# DecadeBox.net
KiCad netlist of a schematic drawn in Altium Designer
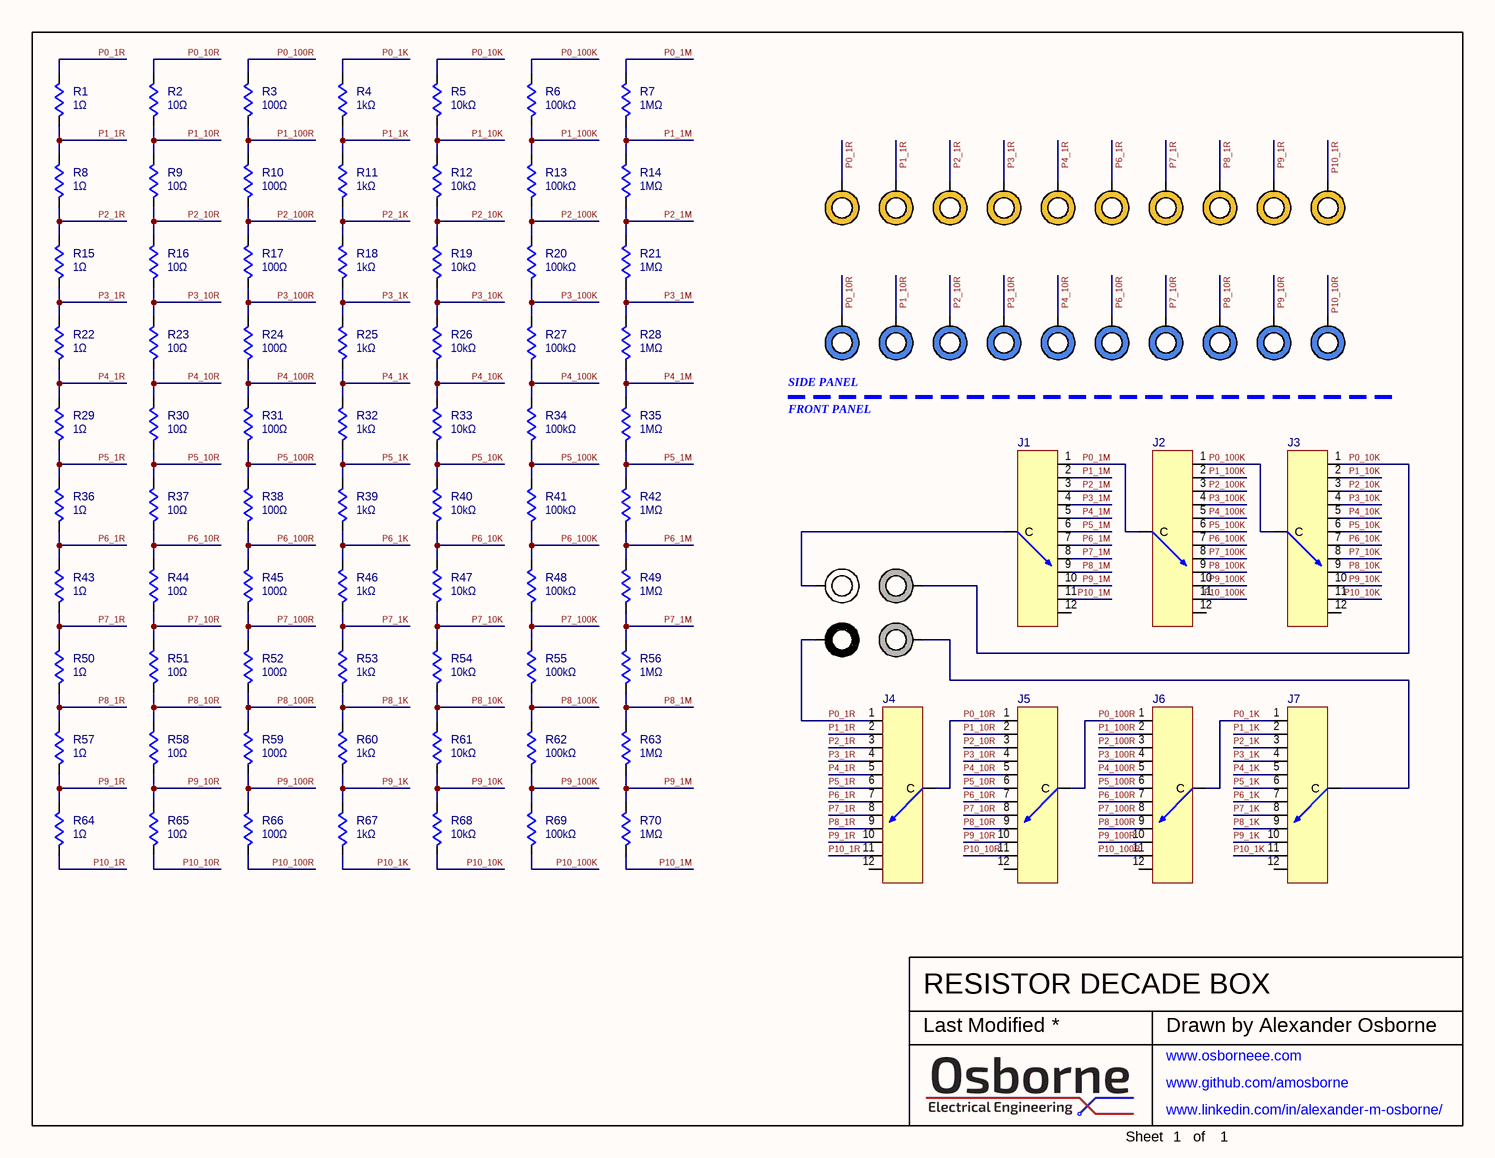
[diagram p0: DecadeBox.SchDoc]

(export (version "E")
  (design (tool "Eeschema 10.0.6"))
  (components
    (comp (ref "J1")
      (value "56SD30-01-1-AJS-ND")
      (description "12 POLE, SINGLE THROW, ROTARY SWITCH")
      (libsource (lib "DecadeBox") (part "ROTARY"))
    )
    (comp (ref "J2")
      (value "56SD30-01-1-AJS-ND")
      (description "12 POLE, SINGLE THROW, ROTARY SWITCH")
      (libsource (lib "DecadeBox") (part "ROTARY"))
    )
    (comp (ref "J3")
      (value "56SD30-01-1-AJS-ND")
      (description "12 POLE, SINGLE THROW, ROTARY SWITCH")
      (libsource (lib "DecadeBox") (part "ROTARY"))
    )
    (comp (ref "J4")
      (value "56SD30-01-1-AJS-ND")
      (description "12 POLE, SINGLE THROW, ROTARY SWITCH")
      (libsource (lib "") (part "ROTARY_1"))
    )
    (comp (ref "J5")
      (value "56SD30-01-1-AJS-ND")
      (description "12 POLE, SINGLE THROW, ROTARY SWITCH")
      (libsource (lib "") (part "ROTARY_1"))
    )
    (comp (ref "J6")
      (value "56SD30-01-1-AJS-ND")
      (description "12 POLE, SINGLE THROW, ROTARY SWITCH")
      (libsource (lib "") (part "ROTARY_1"))
    )
    (comp (ref "J7")
      (value "56SD30-01-1-AJS-ND")
      (description "12 POLE, SINGLE THROW, ROTARY SWITCH")
      (libsource (lib "") (part "ROTARY_1"))
    )
    (comp (ref "J8")
      (value "501-1470-ND")
      (description "BINDING POST, WHITE")
      (libsource (lib "DecadeBox") (part "POST-WHT"))
    )
    (comp (ref "J9")
      (value "501-1714-ND")
      (description "BINDING POST, GRAY")
      (libsource (lib "DecadeBox") (part "POST-GRY"))
    )
    (comp (ref "J10")
      (value "501-2472-ND")
      (description "BINDING POST, BLACK")
      (libsource (lib "DecadeBox") (part "POST-BLK"))
    )
    (comp (ref "J11")
      (value "501-1714-ND")
      (description "BINDING POST, GRAY")
      (libsource (lib "DecadeBox") (part "POST-GRY"))
    )
    (comp (ref "J12")
      (value "501-1082-ND")
      (description "BINDING POST, YELLOW")
      (libsource (lib "DecadeBox") (part "POST-YEL"))
    )
    (comp (ref "J13")
      (value "501-1082-ND")
      (description "BINDING POST, YELLOW")
      (libsource (lib "DecadeBox") (part "POST-YEL"))
    )
    (comp (ref "J14")
      (value "501-1082-ND")
      (description "BINDING POST, YELLOW")
      (libsource (lib "DecadeBox") (part "POST-YEL"))
    )
    (comp (ref "J15")
      (value "501-1082-ND")
      (description "BINDING POST, YELLOW")
      (libsource (lib "DecadeBox") (part "POST-YEL"))
    )
    (comp (ref "J16")
      (value "501-1082-ND")
      (description "BINDING POST, YELLOW")
      (libsource (lib "DecadeBox") (part "POST-YEL"))
    )
    (comp (ref "J17")
      (value "501-1082-ND")
      (description "BINDING POST, YELLOW")
      (libsource (lib "DecadeBox") (part "POST-YEL"))
    )
    (comp (ref "J18")
      (value "501-1082-ND")
      (description "BINDING POST, YELLOW")
      (libsource (lib "DecadeBox") (part "POST-YEL"))
    )
    (comp (ref "J19")
      (value "501-1082-ND")
      (description "BINDING POST, YELLOW")
      (libsource (lib "DecadeBox") (part "POST-YEL"))
    )
    (comp (ref "J20")
      (value "501-1082-ND")
      (description "BINDING POST, YELLOW")
      (libsource (lib "DecadeBox") (part "POST-YEL"))
    )
    (comp (ref "J21")
      (value "501-1082-ND")
      (description "BINDING POST, YELLOW")
      (libsource (lib "DecadeBox") (part "POST-YEL"))
    )
    (comp (ref "J22")
      (value "501-1084-ND")
      (description "BINDING POST, BLUE")
      (libsource (lib "DecadeBox") (part "POST-BLU"))
    )
    (comp (ref "J23")
      (value "501-1084-ND")
      (description "BINDING POST, BLUE")
      (libsource (lib "DecadeBox") (part "POST-BLU"))
    )
    (comp (ref "J24")
      (value "501-1084-ND")
      (description "BINDING POST, BLUE")
      (libsource (lib "DecadeBox") (part "POST-BLU"))
    )
    (comp (ref "J25")
      (value "501-1084-ND")
      (description "BINDING POST, BLUE")
      (libsource (lib "DecadeBox") (part "POST-BLU"))
    )
    (comp (ref "J26")
      (value "501-1084-ND")
      (description "BINDING POST, BLUE")
      (libsource (lib "DecadeBox") (part "POST-BLU"))
    )
    (comp (ref "J27")
      (value "501-1084-ND")
      (description "BINDING POST, BLUE")
      (libsource (lib "DecadeBox") (part "POST-BLU"))
    )
    (comp (ref "J28")
      (value "501-1084-ND")
      (description "BINDING POST, BLUE")
      (libsource (lib "DecadeBox") (part "POST-BLU"))
    )
    (comp (ref "J29")
      (value "501-1084-ND")
      (description "BINDING POST, BLUE")
      (libsource (lib "DecadeBox") (part "POST-BLU"))
    )
    (comp (ref "J30")
      (value "501-1084-ND")
      (description "BINDING POST, BLUE")
      (libsource (lib "DecadeBox") (part "POST-BLU"))
    )
    (comp (ref "J31")
      (value "501-1084-ND")
      (description "BINDING POST, BLUE")
      (libsource (lib "DecadeBox") (part "POST-BLU"))
    )
    (comp (ref "R1")
      (value "1Ω")
      (footprint "MRS25")
      (description "RES 1Ω 1% 50ppm/K 12.5W")
      (fields (field (name "TOLERANCE") "1% + 50ppm/K") (field (name "POWER") "12.5W"))
      (libsource (lib "DecadeBox") (part "RES-1OHM"))
    )
    (comp (ref "R2")
      (value "10Ω")
      (footprint "MRS25")
      (description "RES 10Ω 1% 50ppm/K 10W")
      (fields (field (name "TOLERANCE") "1% + 50ppm/K") (field (name "POWER") "10W"))
      (libsource (lib "DecadeBox") (part "RES-10OHM"))
    )
    (comp (ref "R3")
      (value "100Ω")
      (footprint "MRS25")
      (description "RES 100Ω 1% 50ppm/K 600mW")
      (fields (field (name "TOLERANCE") "1% + 50ppm/K") (field (name "POWER") "600mW"))
      (libsource (lib "DecadeBox") (part "RES-100OHM"))
    )
    (comp (ref "R4")
      (value "1kΩ")
      (footprint "MRS25")
      (description "RES 1kΩ 1% 50ppm/K 600mW")
      (fields (field (name "TOLERANCE") "1% + 50ppm/K") (field (name "POWER") "600mW"))
      (libsource (lib "DecadeBox") (part "RES-1KOHM"))
    )
    (comp (ref "R5")
      (value "10kΩ")
      (footprint "MRS25")
      (description "RES 10kΩ 1% 50ppm/K 600mW")
      (fields (field (name "TOLERANCE") "1% + 50ppm/K") (field (name "POWER") "600mW"))
      (libsource (lib "DecadeBox") (part "RES-10KOHM"))
    )
    (comp (ref "R6")
      (value "100kΩ")
      (footprint "MRS25")
      (description "RES 100kΩ 1% 50ppm/K 600mW")
      (fields (field (name "TOLERANCE") "1% + 50ppm/K") (field (name "POWER") "600mW"))
      (libsource (lib "DecadeBox") (part "RES-100KOHM"))
    )
    (comp (ref "R7")
      (value "1MΩ")
      (footprint "MRS25")
      (description "RES 1MΩ 1% 50ppm/K 600mW")
      (fields (field (name "TOLERANCE") "1% + 50ppm/K") (field (name "POWER") "600mW"))
      (libsource (lib "DecadeBox") (part "RES-1MOHM"))
    )
    (comp (ref "R8")
      (value "1Ω")
      (footprint "MRS25")
      (description "RES 1Ω 1% 50ppm/K 12.5W")
      (fields (field (name "TOLERANCE") "1% + 50ppm/K") (field (name "POWER") "12.5W"))
      (libsource (lib "DecadeBox") (part "RES-1OHM"))
    )
    (comp (ref "R9")
      (value "10Ω")
      (footprint "MRS25")
      (description "RES 10Ω 1% 50ppm/K 10W")
      (fields (field (name "TOLERANCE") "1% + 50ppm/K") (field (name "POWER") "10W"))
      (libsource (lib "DecadeBox") (part "RES-10OHM"))
    )
    (comp (ref "R10")
      (value "100Ω")
      (footprint "MRS25")
      (description "RES 100Ω 1% 50ppm/K 600mW")
      (fields (field (name "TOLERANCE") "1% + 50ppm/K") (field (name "POWER") "600mW"))
      (libsource (lib "DecadeBox") (part "RES-100OHM"))
    )
    (comp (ref "R11")
      (value "1kΩ")
      (footprint "MRS25")
      (description "RES 1kΩ 1% 50ppm/K 600mW")
      (fields (field (name "TOLERANCE") "1% + 50ppm/K") (field (name "POWER") "600mW"))
      (libsource (lib "DecadeBox") (part "RES-1KOHM"))
    )
    (comp (ref "R12")
      (value "10kΩ")
      (footprint "MRS25")
      (description "RES 10kΩ 1% 50ppm/K 600mW")
      (fields (field (name "TOLERANCE") "1% + 50ppm/K") (field (name "POWER") "600mW"))
      (libsource (lib "DecadeBox") (part "RES-10KOHM"))
    )
    (comp (ref "R13")
      (value "100kΩ")
      (footprint "MRS25")
      (description "RES 100kΩ 1% 50ppm/K 600mW")
      (fields (field (name "TOLERANCE") "1% + 50ppm/K") (field (name "POWER") "600mW"))
      (libsource (lib "DecadeBox") (part "RES-100KOHM"))
    )
    (comp (ref "R14")
      (value "1MΩ")
      (footprint "MRS25")
      (description "RES 1MΩ 1% 50ppm/K 600mW")
      (fields (field (name "TOLERANCE") "1% + 50ppm/K") (field (name "POWER") "600mW"))
      (libsource (lib "DecadeBox") (part "RES-1MOHM"))
    )
    (comp (ref "R15")
      (value "1Ω")
      (footprint "MRS25")
      (description "RES 1Ω 1% 50ppm/K 12.5W")
      (fields (field (name "TOLERANCE") "1% + 50ppm/K") (field (name "POWER") "12.5W"))
      (libsource (lib "DecadeBox") (part "RES-1OHM"))
    )
    (comp (ref "R16")
      (value "10Ω")
      (footprint "MRS25")
      (description "RES 10Ω 1% 50ppm/K 10W")
      (fields (field (name "TOLERANCE") "1% + 50ppm/K") (field (name "POWER") "10W"))
      (libsource (lib "DecadeBox") (part "RES-10OHM"))
    )
    (comp (ref "R17")
      (value "100Ω")
      (footprint "MRS25")
      (description "RES 100Ω 1% 50ppm/K 600mW")
      (fields (field (name "TOLERANCE") "1% + 50ppm/K") (field (name "POWER") "600mW"))
      (libsource (lib "DecadeBox") (part "RES-100OHM"))
    )
    (comp (ref "R18")
      (value "1kΩ")
      (footprint "MRS25")
      (description "RES 1kΩ 1% 50ppm/K 600mW")
      (fields (field (name "TOLERANCE") "1% + 50ppm/K") (field (name "POWER") "600mW"))
      (libsource (lib "DecadeBox") (part "RES-1KOHM"))
    )
    (comp (ref "R19")
      (value "10kΩ")
      (footprint "MRS25")
      (description "RES 10kΩ 1% 50ppm/K 600mW")
      (fields (field (name "TOLERANCE") "1% + 50ppm/K") (field (name "POWER") "600mW"))
      (libsource (lib "DecadeBox") (part "RES-10KOHM"))
    )
    (comp (ref "R20")
      (value "100kΩ")
      (footprint "MRS25")
      (description "RES 100kΩ 1% 50ppm/K 600mW")
      (fields (field (name "TOLERANCE") "1% + 50ppm/K") (field (name "POWER") "600mW"))
      (libsource (lib "DecadeBox") (part "RES-100KOHM"))
    )
    (comp (ref "R21")
      (value "1MΩ")
      (footprint "MRS25")
      (description "RES 1MΩ 1% 50ppm/K 600mW")
      (fields (field (name "TOLERANCE") "1% + 50ppm/K") (field (name "POWER") "600mW"))
      (libsource (lib "DecadeBox") (part "RES-1MOHM"))
    )
    (comp (ref "R22")
      (value "1Ω")
      (footprint "MRS25")
      (description "RES 1Ω 1% 50ppm/K 12.5W")
      (fields (field (name "TOLERANCE") "1% + 50ppm/K") (field (name "POWER") "12.5W"))
      (libsource (lib "DecadeBox") (part "RES-1OHM"))
    )
    (comp (ref "R23")
      (value "10Ω")
      (footprint "MRS25")
      (description "RES 10Ω 1% 50ppm/K 10W")
      (fields (field (name "TOLERANCE") "1% + 50ppm/K") (field (name "POWER") "10W"))
      (libsource (lib "DecadeBox") (part "RES-10OHM"))
    )
    (comp (ref "R24")
      (value "100Ω")
      (footprint "MRS25")
      (description "RES 100Ω 1% 50ppm/K 600mW")
      (fields (field (name "TOLERANCE") "1% + 50ppm/K") (field (name "POWER") "600mW"))
      (libsource (lib "DecadeBox") (part "RES-100OHM"))
    )
    (comp (ref "R25")
      (value "1kΩ")
      (footprint "MRS25")
      (description "RES 1kΩ 1% 50ppm/K 600mW")
      (fields (field (name "TOLERANCE") "1% + 50ppm/K") (field (name "POWER") "600mW"))
      (libsource (lib "DecadeBox") (part "RES-1KOHM"))
    )
    (comp (ref "R26")
      (value "10kΩ")
      (footprint "MRS25")
      (description "RES 10kΩ 1% 50ppm/K 600mW")
      (fields (field (name "TOLERANCE") "1% + 50ppm/K") (field (name "POWER") "600mW"))
      (libsource (lib "DecadeBox") (part "RES-10KOHM"))
    )
    (comp (ref "R27")
      (value "100kΩ")
      (footprint "MRS25")
      (description "RES 100kΩ 1% 50ppm/K 600mW")
      (fields (field (name "TOLERANCE") "1% + 50ppm/K") (field (name "POWER") "600mW"))
      (libsource (lib "DecadeBox") (part "RES-100KOHM"))
    )
    (comp (ref "R28")
      (value "1MΩ")
      (footprint "MRS25")
      (description "RES 1MΩ 1% 50ppm/K 600mW")
      (fields (field (name "TOLERANCE") "1% + 50ppm/K") (field (name "POWER") "600mW"))
      (libsource (lib "DecadeBox") (part "RES-1MOHM"))
    )
    (comp (ref "R29")
      (value "1Ω")
      (footprint "MRS25")
      (description "RES 1Ω 1% 50ppm/K 12.5W")
      (fields (field (name "TOLERANCE") "1% + 50ppm/K") (field (name "POWER") "12.5W"))
      (libsource (lib "DecadeBox") (part "RES-1OHM"))
    )
    (comp (ref "R30")
      (value "10Ω")
      (footprint "MRS25")
      (description "RES 10Ω 1% 50ppm/K 10W")
      (fields (field (name "TOLERANCE") "1% + 50ppm/K") (field (name "POWER") "10W"))
      (libsource (lib "DecadeBox") (part "RES-10OHM"))
    )
    (comp (ref "R31")
      (value "100Ω")
      (footprint "MRS25")
      (description "RES 100Ω 1% 50ppm/K 600mW")
      (fields (field (name "TOLERANCE") "1% + 50ppm/K") (field (name "POWER") "600mW"))
      (libsource (lib "DecadeBox") (part "RES-100OHM"))
    )
    (comp (ref "R32")
      (value "1kΩ")
      (footprint "MRS25")
      (description "RES 1kΩ 1% 50ppm/K 600mW")
      (fields (field (name "TOLERANCE") "1% + 50ppm/K") (field (name "POWER") "600mW"))
      (libsource (lib "DecadeBox") (part "RES-1KOHM"))
    )
    (comp (ref "R33")
      (value "10kΩ")
      (footprint "MRS25")
      (description "RES 10kΩ 1% 50ppm/K 600mW")
      (fields (field (name "TOLERANCE") "1% + 50ppm/K") (field (name "POWER") "600mW"))
      (libsource (lib "DecadeBox") (part "RES-10KOHM"))
    )
    (comp (ref "R34")
      (value "100kΩ")
      (footprint "MRS25")
      (description "RES 100kΩ 1% 50ppm/K 600mW")
      (fields (field (name "TOLERANCE") "1% + 50ppm/K") (field (name "POWER") "600mW"))
      (libsource (lib "DecadeBox") (part "RES-100KOHM"))
    )
    (comp (ref "R35")
      (value "1MΩ")
      (footprint "MRS25")
      (description "RES 1MΩ 1% 50ppm/K 600mW")
      (fields (field (name "TOLERANCE") "1% + 50ppm/K") (field (name "POWER") "600mW"))
      (libsource (lib "DecadeBox") (part "RES-1MOHM"))
    )
    (comp (ref "R36")
      (value "1Ω")
      (footprint "MRS25")
      (description "RES 1Ω 1% 50ppm/K 12.5W")
      (fields (field (name "TOLERANCE") "1% + 50ppm/K") (field (name "POWER") "12.5W"))
      (libsource (lib "DecadeBox") (part "RES-1OHM"))
    )
    (comp (ref "R37")
      (value "10Ω")
      (footprint "MRS25")
      (description "RES 10Ω 1% 50ppm/K 10W")
      (fields (field (name "TOLERANCE") "1% + 50ppm/K") (field (name "POWER") "10W"))
      (libsource (lib "DecadeBox") (part "RES-10OHM"))
    )
    (comp (ref "R38")
      (value "100Ω")
      (footprint "MRS25")
      (description "RES 100Ω 1% 50ppm/K 600mW")
      (fields (field (name "TOLERANCE") "1% + 50ppm/K") (field (name "POWER") "600mW"))
      (libsource (lib "DecadeBox") (part "RES-100OHM"))
    )
    (comp (ref "R39")
      (value "1kΩ")
      (footprint "MRS25")
      (description "RES 1kΩ 1% 50ppm/K 600mW")
      (fields (field (name "TOLERANCE") "1% + 50ppm/K") (field (name "POWER") "600mW"))
      (libsource (lib "DecadeBox") (part "RES-1KOHM"))
    )
    (comp (ref "R40")
      (value "10kΩ")
      (footprint "MRS25")
      (description "RES 10kΩ 1% 50ppm/K 600mW")
      (fields (field (name "TOLERANCE") "1% + 50ppm/K") (field (name "POWER") "600mW"))
      (libsource (lib "DecadeBox") (part "RES-10KOHM"))
    )
    (comp (ref "R41")
      (value "100kΩ")
      (footprint "MRS25")
      (description "RES 100kΩ 1% 50ppm/K 600mW")
      (fields (field (name "TOLERANCE") "1% + 50ppm/K") (field (name "POWER") "600mW"))
      (libsource (lib "DecadeBox") (part "RES-100KOHM"))
    )
    (comp (ref "R42")
      (value "1MΩ")
      (footprint "MRS25")
      (description "RES 1MΩ 1% 50ppm/K 600mW")
      (fields (field (name "TOLERANCE") "1% + 50ppm/K") (field (name "POWER") "600mW"))
      (libsource (lib "DecadeBox") (part "RES-1MOHM"))
    )
    (comp (ref "R43")
      (value "1Ω")
      (footprint "MRS25")
      (description "RES 1Ω 1% 50ppm/K 12.5W")
      (fields (field (name "TOLERANCE") "1% + 50ppm/K") (field (name "POWER") "12.5W"))
      (libsource (lib "DecadeBox") (part "RES-1OHM"))
    )
    (comp (ref "R44")
      (value "10Ω")
      (footprint "MRS25")
      (description "RES 10Ω 1% 50ppm/K 10W")
      (fields (field (name "TOLERANCE") "1% + 50ppm/K") (field (name "POWER") "10W"))
      (libsource (lib "DecadeBox") (part "RES-10OHM"))
    )
    (comp (ref "R45")
      (value "100Ω")
      (footprint "MRS25")
      (description "RES 100Ω 1% 50ppm/K 600mW")
      (fields (field (name "TOLERANCE") "1% + 50ppm/K") (field (name "POWER") "600mW"))
      (libsource (lib "DecadeBox") (part "RES-100OHM"))
    )
    (comp (ref "R46")
      (value "1kΩ")
      (footprint "MRS25")
      (description "RES 1kΩ 1% 50ppm/K 600mW")
      (fields (field (name "TOLERANCE") "1% + 50ppm/K") (field (name "POWER") "600mW"))
      (libsource (lib "DecadeBox") (part "RES-1KOHM"))
    )
    (comp (ref "R47")
      (value "10kΩ")
      (footprint "MRS25")
      (description "RES 10kΩ 1% 50ppm/K 600mW")
      (fields (field (name "TOLERANCE") "1% + 50ppm/K") (field (name "POWER") "600mW"))
      (libsource (lib "DecadeBox") (part "RES-10KOHM"))
    )
    (comp (ref "R48")
      (value "100kΩ")
      (footprint "MRS25")
      (description "RES 100kΩ 1% 50ppm/K 600mW")
      (fields (field (name "TOLERANCE") "1% + 50ppm/K") (field (name "POWER") "600mW"))
      (libsource (lib "DecadeBox") (part "RES-100KOHM"))
    )
    (comp (ref "R49")
      (value "1MΩ")
      (footprint "MRS25")
      (description "RES 1MΩ 1% 50ppm/K 600mW")
      (fields (field (name "TOLERANCE") "1% + 50ppm/K") (field (name "POWER") "600mW"))
      (libsource (lib "DecadeBox") (part "RES-1MOHM"))
    )
    (comp (ref "R50")
      (value "1Ω")
      (footprint "MRS25")
      (description "RES 1Ω 1% 50ppm/K 12.5W")
      (fields (field (name "TOLERANCE") "1% + 50ppm/K") (field (name "POWER") "12.5W"))
      (libsource (lib "DecadeBox") (part "RES-1OHM"))
    )
    (comp (ref "R51")
      (value "10Ω")
      (footprint "MRS25")
      (description "RES 10Ω 1% 50ppm/K 10W")
      (fields (field (name "TOLERANCE") "1% + 50ppm/K") (field (name "POWER") "10W"))
      (libsource (lib "DecadeBox") (part "RES-10OHM"))
    )
    (comp (ref "R52")
      (value "100Ω")
      (footprint "MRS25")
      (description "RES 100Ω 1% 50ppm/K 600mW")
      (fields (field (name "TOLERANCE") "1% + 50ppm/K") (field (name "POWER") "600mW"))
      (libsource (lib "DecadeBox") (part "RES-100OHM"))
    )
    (comp (ref "R53")
      (value "1kΩ")
      (footprint "MRS25")
      (description "RES 1kΩ 1% 50ppm/K 600mW")
      (fields (field (name "TOLERANCE") "1% + 50ppm/K") (field (name "POWER") "600mW"))
      (libsource (lib "DecadeBox") (part "RES-1KOHM"))
    )
    (comp (ref "R54")
      (value "10kΩ")
      (footprint "MRS25")
      (description "RES 10kΩ 1% 50ppm/K 600mW")
      (fields (field (name "TOLERANCE") "1% + 50ppm/K") (field (name "POWER") "600mW"))
      (libsource (lib "DecadeBox") (part "RES-10KOHM"))
    )
    (comp (ref "R55")
      (value "100kΩ")
      (footprint "MRS25")
      (description "RES 100kΩ 1% 50ppm/K 600mW")
      (fields (field (name "TOLERANCE") "1% + 50ppm/K") (field (name "POWER") "600mW"))
      (libsource (lib "DecadeBox") (part "RES-100KOHM"))
    )
    (comp (ref "R56")
      (value "1MΩ")
      (footprint "MRS25")
      (description "RES 1MΩ 1% 50ppm/K 600mW")
      (fields (field (name "TOLERANCE") "1% + 50ppm/K") (field (name "POWER") "600mW"))
      (libsource (lib "DecadeBox") (part "RES-1MOHM"))
    )
    (comp (ref "R57")
      (value "1Ω")
      (footprint "MRS25")
      (description "RES 1Ω 1% 50ppm/K 12.5W")
      (fields (field (name "TOLERANCE") "1% + 50ppm/K") (field (name "POWER") "12.5W"))
      (libsource (lib "DecadeBox") (part "RES-1OHM"))
    )
    (comp (ref "R58")
      (value "10Ω")
      (footprint "MRS25")
      (description "RES 10Ω 1% 50ppm/K 10W")
      (fields (field (name "TOLERANCE") "1% + 50ppm/K") (field (name "POWER") "10W"))
      (libsource (lib "DecadeBox") (part "RES-10OHM"))
    )
    (comp (ref "R59")
      (value "100Ω")
      (footprint "MRS25")
      (description "RES 100Ω 1% 50ppm/K 600mW")
      (fields (field (name "TOLERANCE") "1% + 50ppm/K") (field (name "POWER") "600mW"))
      (libsource (lib "DecadeBox") (part "RES-100OHM"))
    )
    (comp (ref "R60")
      (value "1kΩ")
      (footprint "MRS25")
      (description "RES 1kΩ 1% 50ppm/K 600mW")
      (fields (field (name "TOLERANCE") "1% + 50ppm/K") (field (name "POWER") "600mW"))
      (libsource (lib "DecadeBox") (part "RES-1KOHM"))
    )
    (comp (ref "R61")
      (value "10kΩ")
      (footprint "MRS25")
      (description "RES 10kΩ 1% 50ppm/K 600mW")
      (fields (field (name "TOLERANCE") "1% + 50ppm/K") (field (name "POWER") "600mW"))
      (libsource (lib "DecadeBox") (part "RES-10KOHM"))
    )
    (comp (ref "R62")
      (value "100kΩ")
      (footprint "MRS25")
      (description "RES 100kΩ 1% 50ppm/K 600mW")
      (fields (field (name "TOLERANCE") "1% + 50ppm/K") (field (name "POWER") "600mW"))
      (libsource (lib "DecadeBox") (part "RES-100KOHM"))
    )
    (comp (ref "R63")
      (value "1MΩ")
      (footprint "MRS25")
      (description "RES 1MΩ 1% 50ppm/K 600mW")
      (fields (field (name "TOLERANCE") "1% + 50ppm/K") (field (name "POWER") "600mW"))
      (libsource (lib "DecadeBox") (part "RES-1MOHM"))
    )
    (comp (ref "R64")
      (value "1Ω")
      (footprint "MRS25")
      (description "RES 1Ω 1% 50ppm/K 12.5W")
      (fields (field (name "TOLERANCE") "1% + 50ppm/K") (field (name "POWER") "12.5W"))
      (libsource (lib "DecadeBox") (part "RES-1OHM"))
    )
    (comp (ref "R65")
      (value "10Ω")
      (footprint "MRS25")
      (description "RES 10Ω 1% 50ppm/K 10W")
      (fields (field (name "TOLERANCE") "1% + 50ppm/K") (field (name "POWER") "10W"))
      (libsource (lib "DecadeBox") (part "RES-10OHM"))
    )
    (comp (ref "R66")
      (value "100Ω")
      (footprint "MRS25")
      (description "RES 100Ω 1% 50ppm/K 600mW")
      (fields (field (name "TOLERANCE") "1% + 50ppm/K") (field (name "POWER") "600mW"))
      (libsource (lib "DecadeBox") (part "RES-100OHM"))
    )
    (comp (ref "R67")
      (value "1kΩ")
      (footprint "MRS25")
      (description "RES 1kΩ 1% 50ppm/K 600mW")
      (fields (field (name "TOLERANCE") "1% + 50ppm/K") (field (name "POWER") "600mW"))
      (libsource (lib "DecadeBox") (part "RES-1KOHM"))
    )
    (comp (ref "R68")
      (value "10kΩ")
      (footprint "MRS25")
      (description "RES 10kΩ 1% 50ppm/K 600mW")
      (fields (field (name "TOLERANCE") "1% + 50ppm/K") (field (name "POWER") "600mW"))
      (libsource (lib "DecadeBox") (part "RES-10KOHM"))
    )
    (comp (ref "R69")
      (value "100kΩ")
      (footprint "MRS25")
      (description "RES 100kΩ 1% 50ppm/K 600mW")
      (fields (field (name "TOLERANCE") "1% + 50ppm/K") (field (name "POWER") "600mW"))
      (libsource (lib "DecadeBox") (part "RES-100KOHM"))
    )
    (comp (ref "R70")
      (value "1MΩ")
      (footprint "MRS25")
      (description "RES 1MΩ 1% 50ppm/K 600mW")
      (fields (field (name "TOLERANCE") "1% + 50ppm/K") (field (name "POWER") "600mW"))
      (libsource (lib "DecadeBox") (part "RES-1MOHM"))
    )
  )
  (nets
    (net (code "1") (name "/P0_1K") (class "Default")
      (node (ref "J6") (pin "13") (pinfunction "C_13") (pintype "passive"))
      (node (ref "J7") (pin "1") (pintype "passive"))
      (node (ref "R4") (pin "1") (pintype "passive"))
    )
    (net (code "2") (name "/P0_1M") (class "Default")
      (node (ref "J1") (pin "1") (pintype "passive"))
      (node (ref "J2") (pin "13") (pinfunction "C_13") (pintype "passive"))
      (node (ref "R7") (pin "1") (pintype "passive"))
    )
    (net (code "3") (name "/P0_1R") (class "Default")
      (node (ref "J10") (pin "1") (pinfunction "0_1") (pintype "passive"))
      (node (ref "J12") (pin "1") (pinfunction "0_1") (pintype "passive"))
      (node (ref "J4") (pin "1") (pintype "passive"))
      (node (ref "R1") (pin "1") (pintype "passive"))
    )
    (net (code "4") (name "/P0_10K") (class "Default")
      (node (ref "J3") (pin "1") (pintype "passive"))
      (node (ref "J9") (pin "1") (pinfunction "0_1") (pintype "passive"))
      (node (ref "R5") (pin "1") (pintype "passive"))
    )
    (net (code "5") (name "/P0_10R") (class "Default")
      (node (ref "J22") (pin "1") (pinfunction "0_1") (pintype "passive"))
      (node (ref "J4") (pin "13") (pinfunction "C_13") (pintype "passive"))
      (node (ref "J5") (pin "1") (pintype "passive"))
      (node (ref "R2") (pin "1") (pintype "passive"))
    )
    (net (code "6") (name "/P0_100K") (class "Default")
      (node (ref "J2") (pin "1") (pintype "passive"))
      (node (ref "J3") (pin "13") (pinfunction "C_13") (pintype "passive"))
      (node (ref "R6") (pin "1") (pintype "passive"))
    )
    (net (code "7") (name "/P0_100R") (class "Default")
      (node (ref "J5") (pin "13") (pinfunction "C_13") (pintype "passive"))
      (node (ref "J6") (pin "1") (pintype "passive"))
      (node (ref "R3") (pin "1") (pintype "passive"))
    )
    (net (code "8") (name "/P1_1K") (class "Default")
      (node (ref "J7") (pin "2") (pintype "passive"))
      (node (ref "R11") (pin "1") (pintype "passive"))
      (node (ref "R4") (pin "2") (pintype "passive"))
    )
    (net (code "9") (name "/P1_1M") (class "Default")
      (node (ref "J1") (pin "2") (pintype "passive"))
      (node (ref "R14") (pin "1") (pintype "passive"))
      (node (ref "R7") (pin "2") (pintype "passive"))
    )
    (net (code "10") (name "/P1_1R") (class "Default")
      (node (ref "J13") (pin "1") (pinfunction "0_1") (pintype "passive"))
      (node (ref "J4") (pin "2") (pintype "passive"))
      (node (ref "R1") (pin "2") (pintype "passive"))
      (node (ref "R8") (pin "1") (pintype "passive"))
    )
    (net (code "11") (name "/P1_10K") (class "Default")
      (node (ref "J3") (pin "2") (pintype "passive"))
      (node (ref "R12") (pin "1") (pintype "passive"))
      (node (ref "R5") (pin "2") (pintype "passive"))
    )
    (net (code "12") (name "/P1_10R") (class "Default")
      (node (ref "J23") (pin "1") (pinfunction "0_1") (pintype "passive"))
      (node (ref "J5") (pin "2") (pintype "passive"))
      (node (ref "R2") (pin "2") (pintype "passive"))
      (node (ref "R9") (pin "1") (pintype "passive"))
    )
    (net (code "13") (name "/P1_100K") (class "Default")
      (node (ref "J2") (pin "2") (pintype "passive"))
      (node (ref "R13") (pin "1") (pintype "passive"))
      (node (ref "R6") (pin "2") (pintype "passive"))
    )
    (net (code "14") (name "/P1_100R") (class "Default")
      (node (ref "J6") (pin "2") (pintype "passive"))
      (node (ref "R10") (pin "1") (pintype "passive"))
      (node (ref "R3") (pin "2") (pintype "passive"))
    )
    (net (code "15") (name "/P2_1K") (class "Default")
      (node (ref "J7") (pin "3") (pintype "passive"))
      (node (ref "R11") (pin "2") (pintype "passive"))
      (node (ref "R18") (pin "1") (pintype "passive"))
    )
    (net (code "16") (name "/P2_1M") (class "Default")
      (node (ref "J1") (pin "3") (pintype "passive"))
      (node (ref "R14") (pin "2") (pintype "passive"))
      (node (ref "R21") (pin "1") (pintype "passive"))
    )
    (net (code "17") (name "/P2_1R") (class "Default")
      (node (ref "J14") (pin "1") (pinfunction "0_1") (pintype "passive"))
      (node (ref "J4") (pin "3") (pintype "passive"))
      (node (ref "R15") (pin "1") (pintype "passive"))
      (node (ref "R8") (pin "2") (pintype "passive"))
    )
    (net (code "18") (name "/P2_10K") (class "Default")
      (node (ref "J3") (pin "3") (pintype "passive"))
      (node (ref "R12") (pin "2") (pintype "passive"))
      (node (ref "R19") (pin "1") (pintype "passive"))
    )
    (net (code "19") (name "/P2_10R") (class "Default")
      (node (ref "J24") (pin "1") (pinfunction "0_1") (pintype "passive"))
      (node (ref "J5") (pin "3") (pintype "passive"))
      (node (ref "R16") (pin "1") (pintype "passive"))
      (node (ref "R9") (pin "2") (pintype "passive"))
    )
    (net (code "20") (name "/P2_100K") (class "Default")
      (node (ref "J2") (pin "3") (pintype "passive"))
      (node (ref "R13") (pin "2") (pintype "passive"))
      (node (ref "R20") (pin "1") (pintype "passive"))
    )
    (net (code "21") (name "/P2_100R") (class "Default")
      (node (ref "J6") (pin "3") (pintype "passive"))
      (node (ref "R10") (pin "2") (pintype "passive"))
      (node (ref "R17") (pin "1") (pintype "passive"))
    )
    (net (code "22") (name "/P3_1K") (class "Default")
      (node (ref "J7") (pin "4") (pintype "passive"))
      (node (ref "R18") (pin "2") (pintype "passive"))
      (node (ref "R25") (pin "1") (pintype "passive"))
    )
    (net (code "23") (name "/P3_1M") (class "Default")
      (node (ref "J1") (pin "4") (pintype "passive"))
      (node (ref "R21") (pin "2") (pintype "passive"))
      (node (ref "R28") (pin "1") (pintype "passive"))
    )
    (net (code "24") (name "/P3_1R") (class "Default")
      (node (ref "J15") (pin "1") (pinfunction "0_1") (pintype "passive"))
      (node (ref "J4") (pin "4") (pintype "passive"))
      (node (ref "R15") (pin "2") (pintype "passive"))
      (node (ref "R22") (pin "1") (pintype "passive"))
    )
    (net (code "25") (name "/P3_10K") (class "Default")
      (node (ref "J3") (pin "4") (pintype "passive"))
      (node (ref "R19") (pin "2") (pintype "passive"))
      (node (ref "R26") (pin "1") (pintype "passive"))
    )
    (net (code "26") (name "/P3_10R") (class "Default")
      (node (ref "J25") (pin "1") (pinfunction "0_1") (pintype "passive"))
      (node (ref "J5") (pin "4") (pintype "passive"))
      (node (ref "R16") (pin "2") (pintype "passive"))
      (node (ref "R23") (pin "1") (pintype "passive"))
    )
    (net (code "27") (name "/P3_100K") (class "Default")
      (node (ref "J2") (pin "4") (pintype "passive"))
      (node (ref "R20") (pin "2") (pintype "passive"))
      (node (ref "R27") (pin "1") (pintype "passive"))
    )
    (net (code "28") (name "/P3_100R") (class "Default")
      (node (ref "J6") (pin "4") (pintype "passive"))
      (node (ref "R17") (pin "2") (pintype "passive"))
      (node (ref "R24") (pin "1") (pintype "passive"))
    )
    (net (code "29") (name "/P4_1K") (class "Default")
      (node (ref "J7") (pin "5") (pintype "passive"))
      (node (ref "R25") (pin "2") (pintype "passive"))
      (node (ref "R32") (pin "1") (pintype "passive"))
    )
    (net (code "30") (name "/P4_1M") (class "Default")
      (node (ref "J1") (pin "5") (pintype "passive"))
      (node (ref "R28") (pin "2") (pintype "passive"))
      (node (ref "R35") (pin "1") (pintype "passive"))
    )
    (net (code "31") (name "/P4_1R") (class "Default")
      (node (ref "J16") (pin "1") (pinfunction "0_1") (pintype "passive"))
      (node (ref "J4") (pin "5") (pintype "passive"))
      (node (ref "R22") (pin "2") (pintype "passive"))
      (node (ref "R29") (pin "1") (pintype "passive"))
    )
    (net (code "32") (name "/P4_10K") (class "Default")
      (node (ref "J3") (pin "5") (pintype "passive"))
      (node (ref "R26") (pin "2") (pintype "passive"))
      (node (ref "R33") (pin "1") (pintype "passive"))
    )
    (net (code "33") (name "/P4_10R") (class "Default")
      (node (ref "J26") (pin "1") (pinfunction "0_1") (pintype "passive"))
      (node (ref "J5") (pin "5") (pintype "passive"))
      (node (ref "R23") (pin "2") (pintype "passive"))
      (node (ref "R30") (pin "1") (pintype "passive"))
    )
    (net (code "34") (name "/P4_100K") (class "Default")
      (node (ref "J2") (pin "5") (pintype "passive"))
      (node (ref "R27") (pin "2") (pintype "passive"))
      (node (ref "R34") (pin "1") (pintype "passive"))
    )
    (net (code "35") (name "/P4_100R") (class "Default")
      (node (ref "J6") (pin "5") (pintype "passive"))
      (node (ref "R24") (pin "2") (pintype "passive"))
      (node (ref "R31") (pin "1") (pintype "passive"))
    )
    (net (code "36") (name "/P5_1K") (class "Default")
      (node (ref "J7") (pin "6") (pintype "passive"))
      (node (ref "R32") (pin "2") (pintype "passive"))
      (node (ref "R39") (pin "1") (pintype "passive"))
    )
    (net (code "37") (name "/P5_1M") (class "Default")
      (node (ref "J1") (pin "6") (pintype "passive"))
      (node (ref "R35") (pin "2") (pintype "passive"))
      (node (ref "R42") (pin "1") (pintype "passive"))
    )
    (net (code "38") (name "/P5_1R") (class "Default")
      (node (ref "J4") (pin "6") (pintype "passive"))
      (node (ref "R29") (pin "2") (pintype "passive"))
      (node (ref "R36") (pin "1") (pintype "passive"))
    )
    (net (code "39") (name "/P5_10K") (class "Default")
      (node (ref "J3") (pin "6") (pintype "passive"))
      (node (ref "R33") (pin "2") (pintype "passive"))
      (node (ref "R40") (pin "1") (pintype "passive"))
    )
    (net (code "40") (name "/P5_10R") (class "Default")
      (node (ref "J5") (pin "6") (pintype "passive"))
      (node (ref "R30") (pin "2") (pintype "passive"))
      (node (ref "R37") (pin "1") (pintype "passive"))
    )
    (net (code "41") (name "/P5_100K") (class "Default")
      (node (ref "J2") (pin "6") (pintype "passive"))
      (node (ref "R34") (pin "2") (pintype "passive"))
      (node (ref "R41") (pin "1") (pintype "passive"))
    )
    (net (code "42") (name "/P5_100R") (class "Default")
      (node (ref "J6") (pin "6") (pintype "passive"))
      (node (ref "R31") (pin "2") (pintype "passive"))
      (node (ref "R38") (pin "1") (pintype "passive"))
    )
    (net (code "43") (name "/P6_1K") (class "Default")
      (node (ref "J7") (pin "7") (pintype "passive"))
      (node (ref "R39") (pin "2") (pintype "passive"))
      (node (ref "R46") (pin "1") (pintype "passive"))
    )
    (net (code "44") (name "/P6_1M") (class "Default")
      (node (ref "J1") (pin "7") (pintype "passive"))
      (node (ref "R42") (pin "2") (pintype "passive"))
      (node (ref "R49") (pin "1") (pintype "passive"))
    )
    (net (code "45") (name "/P6_1R") (class "Default")
      (node (ref "J17") (pin "1") (pinfunction "0_1") (pintype "passive"))
      (node (ref "J4") (pin "7") (pintype "passive"))
      (node (ref "R36") (pin "2") (pintype "passive"))
      (node (ref "R43") (pin "1") (pintype "passive"))
    )
    (net (code "46") (name "/P6_10K") (class "Default")
      (node (ref "J3") (pin "7") (pintype "passive"))
      (node (ref "R40") (pin "2") (pintype "passive"))
      (node (ref "R47") (pin "1") (pintype "passive"))
    )
    (net (code "47") (name "/P6_10R") (class "Default")
      (node (ref "J27") (pin "1") (pinfunction "0_1") (pintype "passive"))
      (node (ref "J5") (pin "7") (pintype "passive"))
      (node (ref "R37") (pin "2") (pintype "passive"))
      (node (ref "R44") (pin "1") (pintype "passive"))
    )
    (net (code "48") (name "/P6_100K") (class "Default")
      (node (ref "J2") (pin "7") (pintype "passive"))
      (node (ref "R41") (pin "2") (pintype "passive"))
      (node (ref "R48") (pin "1") (pintype "passive"))
    )
    (net (code "49") (name "/P6_100R") (class "Default")
      (node (ref "J6") (pin "7") (pintype "passive"))
      (node (ref "R38") (pin "2") (pintype "passive"))
      (node (ref "R45") (pin "1") (pintype "passive"))
    )
    (net (code "50") (name "/P7_1K") (class "Default")
      (node (ref "J7") (pin "8") (pintype "passive"))
      (node (ref "R46") (pin "2") (pintype "passive"))
      (node (ref "R53") (pin "1") (pintype "passive"))
    )
    (net (code "51") (name "/P7_1M") (class "Default")
      (node (ref "J1") (pin "8") (pintype "passive"))
      (node (ref "R49") (pin "2") (pintype "passive"))
      (node (ref "R56") (pin "1") (pintype "passive"))
    )
    (net (code "52") (name "/P7_1R") (class "Default")
      (node (ref "J18") (pin "1") (pinfunction "0_1") (pintype "passive"))
      (node (ref "J4") (pin "8") (pintype "passive"))
      (node (ref "R43") (pin "2") (pintype "passive"))
      (node (ref "R50") (pin "1") (pintype "passive"))
    )
    (net (code "53") (name "/P7_10K") (class "Default")
      (node (ref "J3") (pin "8") (pintype "passive"))
      (node (ref "R47") (pin "2") (pintype "passive"))
      (node (ref "R54") (pin "1") (pintype "passive"))
    )
    (net (code "54") (name "/P7_10R") (class "Default")
      (node (ref "J28") (pin "1") (pinfunction "0_1") (pintype "passive"))
      (node (ref "J5") (pin "8") (pintype "passive"))
      (node (ref "R44") (pin "2") (pintype "passive"))
      (node (ref "R51") (pin "1") (pintype "passive"))
    )
    (net (code "55") (name "/P7_100K") (class "Default")
      (node (ref "J2") (pin "8") (pintype "passive"))
      (node (ref "R48") (pin "2") (pintype "passive"))
      (node (ref "R55") (pin "1") (pintype "passive"))
    )
    (net (code "56") (name "/P7_100R") (class "Default")
      (node (ref "J6") (pin "8") (pintype "passive"))
      (node (ref "R45") (pin "2") (pintype "passive"))
      (node (ref "R52") (pin "1") (pintype "passive"))
    )
    (net (code "57") (name "/P8_1K") (class "Default")
      (node (ref "J7") (pin "9") (pintype "passive"))
      (node (ref "R53") (pin "2") (pintype "passive"))
      (node (ref "R60") (pin "1") (pintype "passive"))
    )
    (net (code "58") (name "/P8_1M") (class "Default")
      (node (ref "J1") (pin "9") (pintype "passive"))
      (node (ref "R56") (pin "2") (pintype "passive"))
      (node (ref "R63") (pin "1") (pintype "passive"))
    )
    (net (code "59") (name "/P8_1R") (class "Default")
      (node (ref "J19") (pin "1") (pinfunction "0_1") (pintype "passive"))
      (node (ref "J4") (pin "9") (pintype "passive"))
      (node (ref "R50") (pin "2") (pintype "passive"))
      (node (ref "R57") (pin "1") (pintype "passive"))
    )
    (net (code "60") (name "/P8_10K") (class "Default")
      (node (ref "J3") (pin "9") (pintype "passive"))
      (node (ref "R54") (pin "2") (pintype "passive"))
      (node (ref "R61") (pin "1") (pintype "passive"))
    )
    (net (code "61") (name "/P8_10R") (class "Default")
      (node (ref "J29") (pin "1") (pinfunction "0_1") (pintype "passive"))
      (node (ref "J5") (pin "9") (pintype "passive"))
      (node (ref "R51") (pin "2") (pintype "passive"))
      (node (ref "R58") (pin "1") (pintype "passive"))
    )
    (net (code "62") (name "/P8_100K") (class "Default")
      (node (ref "J2") (pin "9") (pintype "passive"))
      (node (ref "R55") (pin "2") (pintype "passive"))
      (node (ref "R62") (pin "1") (pintype "passive"))
    )
    (net (code "63") (name "/P8_100R") (class "Default")
      (node (ref "J6") (pin "9") (pintype "passive"))
      (node (ref "R52") (pin "2") (pintype "passive"))
      (node (ref "R59") (pin "1") (pintype "passive"))
    )
    (net (code "64") (name "/P9_1K") (class "Default")
      (node (ref "J7") (pin "10") (pintype "passive"))
      (node (ref "R60") (pin "2") (pintype "passive"))
      (node (ref "R67") (pin "1") (pintype "passive"))
    )
    (net (code "65") (name "/P9_1M") (class "Default")
      (node (ref "J1") (pin "10") (pintype "passive"))
      (node (ref "R63") (pin "2") (pintype "passive"))
      (node (ref "R70") (pin "1") (pintype "passive"))
    )
    (net (code "66") (name "/P9_1R") (class "Default")
      (node (ref "J20") (pin "1") (pinfunction "0_1") (pintype "passive"))
      (node (ref "J4") (pin "10") (pintype "passive"))
      (node (ref "R57") (pin "2") (pintype "passive"))
      (node (ref "R64") (pin "1") (pintype "passive"))
    )
    (net (code "67") (name "/P9_10K") (class "Default")
      (node (ref "J3") (pin "10") (pintype "passive"))
      (node (ref "R61") (pin "2") (pintype "passive"))
      (node (ref "R68") (pin "1") (pintype "passive"))
    )
    (net (code "68") (name "/P9_10R") (class "Default")
      (node (ref "J30") (pin "1") (pinfunction "0_1") (pintype "passive"))
      (node (ref "J5") (pin "10") (pintype "passive"))
      (node (ref "R58") (pin "2") (pintype "passive"))
      (node (ref "R65") (pin "1") (pintype "passive"))
    )
    (net (code "69") (name "/P9_100K") (class "Default")
      (node (ref "J2") (pin "10") (pintype "passive"))
      (node (ref "R62") (pin "2") (pintype "passive"))
      (node (ref "R69") (pin "1") (pintype "passive"))
    )
    (net (code "70") (name "/P9_100R") (class "Default")
      (node (ref "J6") (pin "10") (pintype "passive"))
      (node (ref "R59") (pin "2") (pintype "passive"))
      (node (ref "R66") (pin "1") (pintype "passive"))
    )
    (net (code "71") (name "/P10_1K") (class "Default")
      (node (ref "J7") (pin "11") (pintype "passive"))
      (node (ref "R67") (pin "2") (pintype "passive"))
    )
    (net (code "72") (name "/P10_1M") (class "Default")
      (node (ref "J1") (pin "11") (pintype "passive"))
      (node (ref "R70") (pin "2") (pintype "passive"))
    )
    (net (code "73") (name "/P10_1R") (class "Default")
      (node (ref "J21") (pin "1") (pinfunction "0_1") (pintype "passive"))
      (node (ref "J4") (pin "11") (pintype "passive"))
      (node (ref "R64") (pin "2") (pintype "passive"))
    )
    (net (code "74") (name "/P10_10K") (class "Default")
      (node (ref "J3") (pin "11") (pintype "passive"))
      (node (ref "R68") (pin "2") (pintype "passive"))
    )
    (net (code "75") (name "/P10_10R") (class "Default")
      (node (ref "J31") (pin "1") (pinfunction "0_1") (pintype "passive"))
      (node (ref "J5") (pin "11") (pintype "passive"))
      (node (ref "R65") (pin "2") (pintype "passive"))
    )
    (net (code "76") (name "/P10_100K") (class "Default")
      (node (ref "J2") (pin "11") (pintype "passive"))
      (node (ref "R69") (pin "2") (pintype "passive"))
    )
    (net (code "77") (name "/P10_100R") (class "Default")
      (node (ref "J6") (pin "11") (pintype "passive"))
      (node (ref "R66") (pin "2") (pintype "passive"))
    )
    (net (code "78") (name "Net-(J1-C)") (class "Default")
      (node (ref "J1") (pin "13") (pinfunction "C_13") (pintype "passive"))
      (node (ref "J8") (pin "1") (pinfunction "0_1") (pintype "passive"))
    )
    (net (code "79") (name "Net-(J11-0)") (class "Default")
      (node (ref "J11") (pin "1") (pinfunction "0_1") (pintype "passive"))
      (node (ref "J7") (pin "13") (pinfunction "C_13") (pintype "passive"))
    )
    (net (code "80") (name "unconnected-(J1-Pad12)") (class "Default")
      (node (ref "J1") (pin "12") (pintype "passive"))
    )
    (net (code "81") (name "unconnected-(J2-Pad12)") (class "Default")
      (node (ref "J2") (pin "12") (pintype "passive"))
    )
    (net (code "82") (name "unconnected-(J3-Pad12)") (class "Default")
      (node (ref "J3") (pin "12") (pintype "passive"))
    )
    (net (code "83") (name "unconnected-(J4-Pad12)") (class "Default")
      (node (ref "J4") (pin "12") (pintype "passive"))
    )
    (net (code "84") (name "unconnected-(J5-Pad12)") (class "Default")
      (node (ref "J5") (pin "12") (pintype "passive"))
    )
    (net (code "85") (name "unconnected-(J6-Pad12)") (class "Default")
      (node (ref "J6") (pin "12") (pintype "passive"))
    )
    (net (code "86") (name "unconnected-(J7-Pad12)") (class "Default")
      (node (ref "J7") (pin "12") (pintype "passive"))
    )
  )
)
